# pic24.net
KiCad netlist of a schematic drawn in EasyEDA
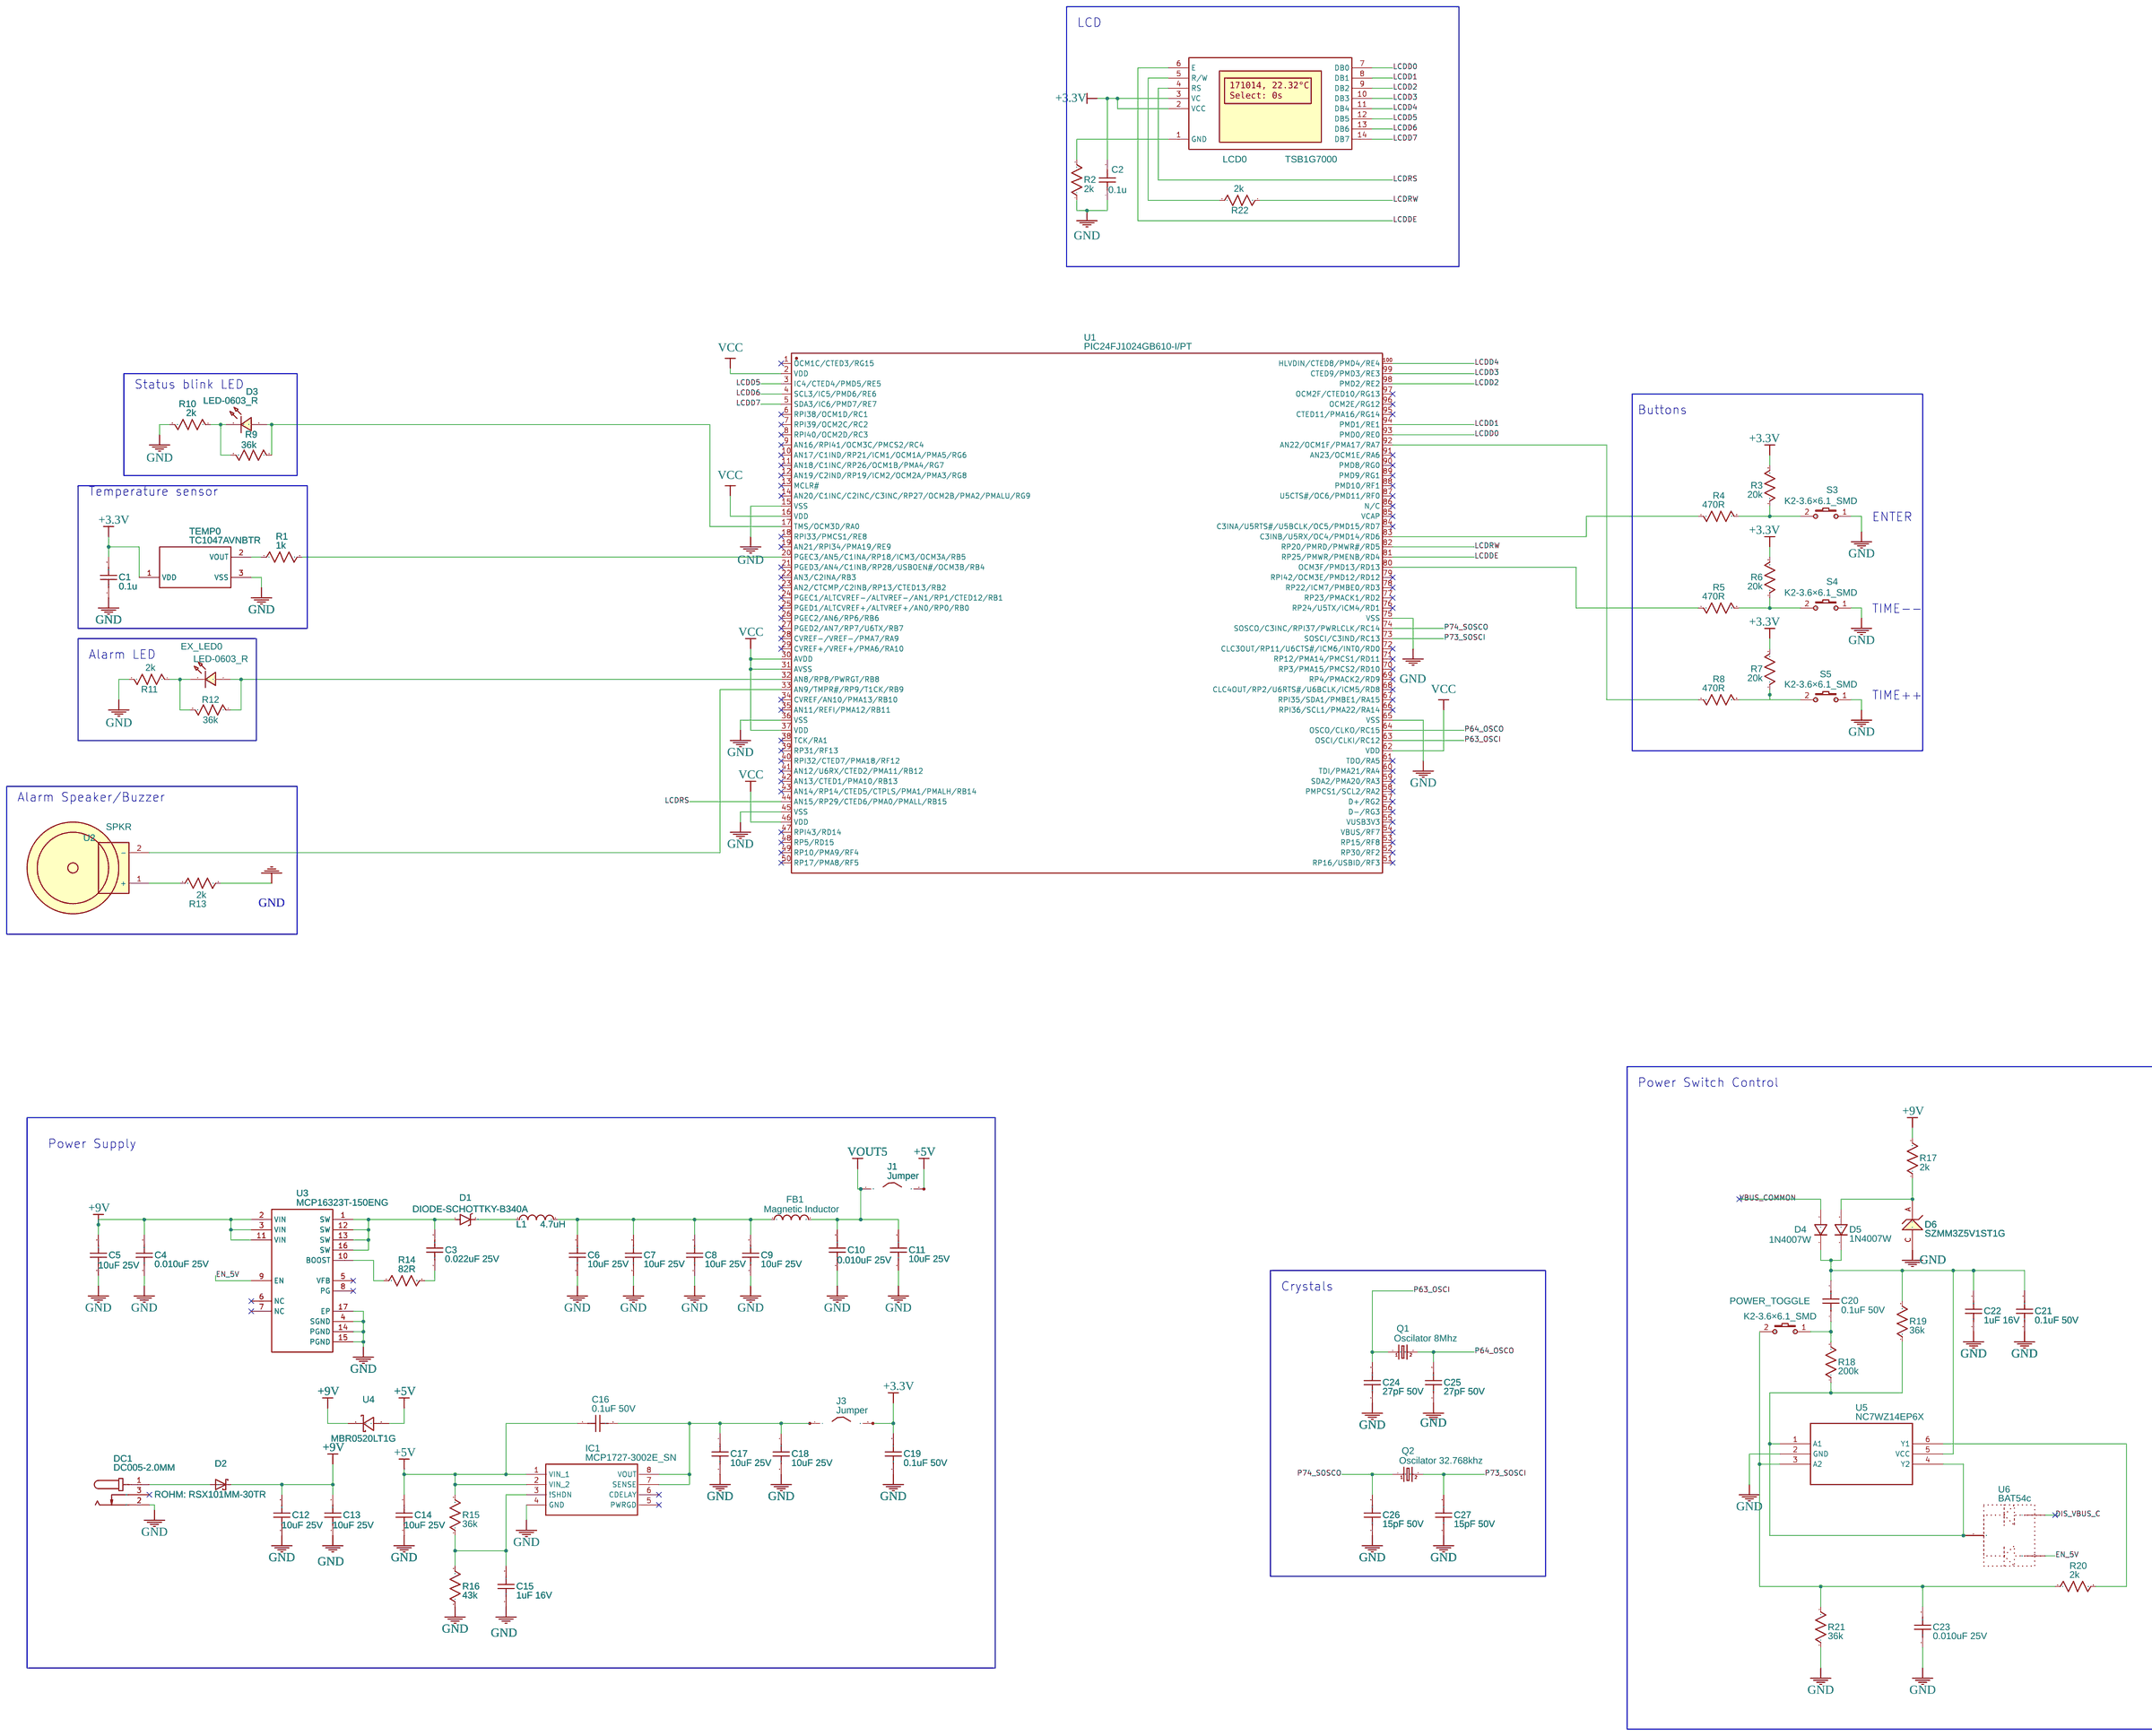
[diagram p0: schematic sheet]

(export (version "E")
  (design (tool "Eeschema 10.0.6"))
  (components
    (comp (ref "C1") (value "0.1u") (libsource (lib "") (part "C_0603_US")))
    (comp (ref "C2") (value "0.1u") (libsource (lib "") (part "C_0603_US")))
    (comp (ref "C3") (value "0.022uF 25V") (libsource (lib "") (part "C_0603_US")))
    (comp (ref "C4") (value "0.010uF 25V") (libsource (lib "") (part "C_0603_US")))
    (comp (ref "C5") (value "10uF 25V") (libsource (lib "") (part "C_0805_US")))
    (comp (ref "C6") (value "10uF 25V") (libsource (lib "") (part "C_0603_US")))
    (comp (ref "C7") (value "10uF 25V") (libsource (lib "") (part "C_0603_US")))
    (comp (ref "C8") (value "10uF 25V") (libsource (lib "") (part "C_0603_US")))
    (comp (ref "C9") (value "10uF 25V") (libsource (lib "") (part "C_0603_US")))
    (comp (ref "C10") (value "0.010uF 25V") (libsource (lib "") (part "C_0805_US")))
    (comp (ref "C11") (value "10uF 25V") (libsource (lib "") (part "C_0603_US")))
    (comp (ref "C12") (value "10uF 25V") (libsource (lib "") (part "C_0805_US")))
    (comp (ref "C13") (value "10uF 25V") (libsource (lib "") (part "C_0805_US")))
    (comp (ref "C14") (value "10uF 25V") (libsource (lib "") (part "C_0805_US")))
    (comp (ref "C15") (value "1uF 16V") (libsource (lib "") (part "C_0603_US")))
    (comp (ref "C16") (value "0.1uF 50V") (libsource (lib "") (part "C_0603_US_1")))
    (comp (ref "C17") (value "10uF 25V") (libsource (lib "") (part "C_0805_US_1")))
    (comp (ref "C18") (value "10uF 25V") (libsource (lib "") (part "C_0805_US_1")))
    (comp (ref "C19") (value "0.1uF 50V") (libsource (lib "") (part "C_0603_US")))
    (comp (ref "C20") (value "0.1uF 50V") (libsource (lib "") (part "C_0603_US")))
    (comp (ref "C21") (value "0.1uF 50V") (libsource (lib "") (part "C_0603_US")))
    (comp (ref "C22") (value "1uF 16V") (libsource (lib "") (part "C_0603_US")))
    (comp (ref "C23") (value "0.010uF 25V") (libsource (lib "") (part "C_0603_US")))
    (comp (ref "C24") (value "27pF 50V") (libsource (lib "") (part "C_0603_US")))
    (comp (ref "C25") (value "27pF 50V") (libsource (lib "") (part "C_0603_US")))
    (comp (ref "C26") (value "15pF 50V") (libsource (lib "") (part "C_0603_US")))
    (comp (ref "C27") (value "15pF 50V") (libsource (lib "") (part "C_0603_US")))
    (comp (ref "D1") (value "DIODE-SCHOTTKY-B340A") (libsource (lib "") (part "DIODE-SCHOTTKY-B340A")))
    (comp (ref "D2")
      (value "ROHM: RSX101MM-30TR")
      (fields (field (name "BOM_Supplier Part") "755-RSX101MM-30TR"))
      (libsource (lib "") (part "ROHM{colon} RSX101MM-30TR"))
    )
    (comp (ref "D3")
      (value "LED-0603_R")
      (fields
        (field (name "BOM_Manufacturer Part") "19-217/R6C-AL1M2VY/3T")
        (field (name "BOM_Supplier Part") "C72044")
      )
      (libsource (lib "") (part "LED-0603_R"))
    )
    (comp (ref "D4")
      (value "1N4007W")
      (fields (field (name "BOM_Supplier Part") "C328592"))
      (libsource (lib "") (part "1N4007W"))
    )
    (comp (ref "D5")
      (value "1N4007W")
      (fields (field (name "BOM_Supplier Part") "C328592"))
      (libsource (lib "") (part "1N4007W"))
    )
    (comp (ref "D6") (value "SZMM3Z5V1ST1G") (libsource (lib "") (part "SZMM3Z5V1ST1G")))
    (comp (ref "DC1")
      (value "DC005-2.0MM")
      (fields (field (name "BOM_Supplier Part") "C111567"))
      (libsource (lib "") (part "DC005-2.0MM"))
    )
    (comp (ref "EX_LED0")
      (value "LED-0603_R")
      (fields
        (field (name "BOM_Manufacturer Part") "19-217/R6C-AL1M2VY/3T")
        (field (name "BOM_Supplier Part") "C72044")
      )
      (libsource (lib "") (part "LED-0603_R_1"))
    )
    (comp (ref "FB1") (value "Magnetic Inductor") (libsource (lib "") (part "INDUCTOR")))
    (comp (ref "IC1") (value "MCP1727-3002E_SN") (libsource (lib "") (part "MCP1727-3002E_SN")))
    (comp (ref "J1")
      (value "Jumper")
      (fields (field (name "BOM_Manufacturer Part") "NONE"))
      (libsource (lib "") (part "JUMPER"))
    )
    (comp (ref "J3")
      (value "Jumper")
      (fields (field (name "BOM_Manufacturer Part") "NONE"))
      (libsource (lib "") (part "JUMPER"))
    )
    (comp (ref "L1") (value "4.7uH") (libsource (lib "") (part "L0603_US")))
    (comp (ref "LCD0") (value "TSB1G7000") (libsource (lib "") (part "TSB1G7000")))
    (comp (ref "POWER_TOGGLE")
      (value "K2-3.6×6.1_SMD")
      (fields
        (field (name "BOM_Manufacturer Part") "K2-1107ST-A4SW-06")
        (field (name "BOM_Supplier Part") "C118141")
      )
      (libsource (lib "") (part "K2-3.6×6.1_SMD_1"))
    )
    (comp (ref "Q1") (value "Oscilator 8Mhz") (libsource (lib "") (part "Oscilator 8Mhz")))
    (comp (ref "Q2") (value "Oscilator 32.768khz") (libsource (lib "") (part "Oscilator 8Mhz")))
    (comp (ref "R1") (value "1k") (libsource (lib "") (part "R_0603_US_3")))
    (comp (ref "R2") (value "2k") (libsource (lib "") (part "R_0603_US_1")))
    (comp (ref "R3") (value "20k") (libsource (lib "") (part "R_0603_US_4")))
    (comp (ref "R4") (value "470R") (libsource (lib "") (part "R_0603_US_2")))
    (comp (ref "R5") (value "470R") (libsource (lib "") (part "R_0603_US_2")))
    (comp (ref "R6") (value "20k") (libsource (lib "") (part "R_0603_US_4")))
    (comp (ref "R7") (value "20k") (libsource (lib "") (part "R_0603_US_4")))
    (comp (ref "R8") (value "470R") (libsource (lib "") (part "R_0603_US_2")))
    (comp (ref "R9") (value "36k") (libsource (lib "") (part "R_0603_US")))
    (comp (ref "R10") (value "2k") (libsource (lib "") (part "R_0603_US")))
    (comp (ref "R11") (value "2k") (libsource (lib "") (part "R_0603_US")))
    (comp (ref "R12") (value "36k") (libsource (lib "") (part "R_0603_US")))
    (comp (ref "R13") (value "2k") (libsource (lib "") (part "R_0603_US_5")))
    (comp (ref "R14") (value "82R") (libsource (lib "") (part "R_0603_US_3")))
    (comp (ref "R15") (value "36k") (libsource (lib "") (part "R_0603_US_1")))
    (comp (ref "R16") (value "43k") (libsource (lib "") (part "R_0603_US_1")))
    (comp (ref "R17") (value "2k") (libsource (lib "") (part "R_0603_US_1")))
    (comp (ref "R18") (value "200k") (libsource (lib "") (part "R_0603_US_1")))
    (comp (ref "R19") (value "36k") (libsource (lib "") (part "R_0603_US_1")))
    (comp (ref "R20") (value "2k") (libsource (lib "") (part "R_0603_US_3")))
    (comp (ref "R21") (value "36k") (libsource (lib "") (part "R_0603_US_1")))
    (comp (ref "R22") (value "2k") (libsource (lib "") (part "R_0603_US_3")))
    (comp (ref "S3")
      (value "K2-3.6×6.1_SMD")
      (fields
        (field (name "BOM_Manufacturer Part") "K2-1107ST-A4SW-06")
        (field (name "BOM_Supplier Part") "C118141")
      )
      (libsource (lib "") (part "K2-3.6×6.1_SMD"))
    )
    (comp (ref "S4")
      (value "K2-3.6×6.1_SMD")
      (fields
        (field (name "BOM_Manufacturer Part") "K2-1107ST-A4SW-06")
        (field (name "BOM_Supplier Part") "C118141")
      )
      (libsource (lib "") (part "K2-3.6×6.1_SMD"))
    )
    (comp (ref "S5")
      (value "K2-3.6×6.1_SMD")
      (fields
        (field (name "BOM_Manufacturer Part") "K2-1107ST-A4SW-06")
        (field (name "BOM_Supplier Part") "C118141")
      )
      (libsource (lib "") (part "K2-3.6×6.1_SMD"))
    )
    (comp (ref "TEMP0")
      (value "TC1047AVNBTR")
      (fields (field (name "BOM_Supplier Part") "C50052"))
      (libsource (lib "") (part "TC1047AVNBTR"))
    )
    (comp (ref "U1")
      (value "PIC24FJ1024GB610-I/PT")
      (fields (field (name "BOM_Supplier Part") "C635616"))
      (libsource (lib "") (part "PIC24FJ1024GB610-I/PT"))
    )
    (comp (ref "U2") (value "SPKR") (libsource (lib "") (part "SPKR")))
    (comp (ref "U3") (value "MCP16323T-150ENG") (libsource (lib "") (part "MCP16323T-150ENG")))
    (comp (ref "U4") (value "MBR0520LT1G") (libsource (lib "") (part "MBR0520LT1G")))
    (comp (ref "U5") (value "NC7WZ14EP6X") (libsource (lib "") (part "NC7WZ14EP6X")))
    (comp (ref "U6") (value "BAT54c") (libsource (lib "") (part "BAT54c")))
  )
  (nets
    (net (code "1") (name "+3.3V") (class "Default")
      (node (ref "C1") (pin "2") (pinfunction "2_2") (pintype "unspecified"))
      (node (ref "C19") (pin "2") (pinfunction "2_2") (pintype "unspecified"))
      (node (ref "C2") (pin "2") (pinfunction "2_2") (pintype "unspecified"))
      (node (ref "J3") (pin "2") (pinfunction "2_2") (pintype "unspecified"))
      (node (ref "LCD0") (pin "2") (pinfunction "VCC_2") (pintype "unspecified"))
      (node (ref "LCD0") (pin "3") (pinfunction "VC_3") (pintype "unspecified"))
      (node (ref "R3") (pin "2") (pinfunction "2_2") (pintype "unspecified"))
      (node (ref "R6") (pin "2") (pinfunction "2_2") (pintype "unspecified"))
      (node (ref "R7") (pin "2") (pinfunction "2_2") (pintype "unspecified"))
      (node (ref "TEMP0") (pin "1") (pinfunction "VDD_1") (pintype "passive"))
    )
    (net (code "2") (name "+5V") (class "Default")
      (node (ref "C14") (pin "2") (pinfunction "2_2") (pintype "unspecified"))
      (node (ref "C16") (pin "1") (pinfunction "1_1") (pintype "unspecified"))
      (node (ref "IC1") (pin "1") (pinfunction "VIN_1_1") (pintype "bidirectional"))
      (node (ref "IC1") (pin "2") (pinfunction "VIN_2_2") (pintype "bidirectional"))
      (node (ref "J1") (pin "2") (pinfunction "2_2") (pintype "unspecified"))
      (node (ref "R15") (pin "2") (pinfunction "2_2") (pintype "unspecified"))
      (node (ref "U4") (pin "1") (pinfunction "A_1") (pintype "unspecified"))
    )
    (net (code "3") (name "+9V") (class "Default")
      (node (ref "C12") (pin "2") (pinfunction "2_2") (pintype "unspecified"))
      (node (ref "C13") (pin "2") (pinfunction "2_2") (pintype "unspecified"))
      (node (ref "C4") (pin "2") (pinfunction "2_2") (pintype "unspecified"))
      (node (ref "C5") (pin "2") (pinfunction "2_2") (pintype "unspecified"))
      (node (ref "D2") (pin "2") (pinfunction "C_2") (pintype "unspecified"))
      (node (ref "R17") (pin "2") (pinfunction "2_2") (pintype "unspecified"))
      (node (ref "U3") (pin "11") (pinfunction "VIN_11") (pintype "passive"))
      (node (ref "U3") (pin "2") (pinfunction "VIN_2") (pintype "passive"))
      (node (ref "U3") (pin "3") (pinfunction "VIN_3") (pintype "passive"))
      (node (ref "U4") (pin "2") (pinfunction "K_2") (pintype "unspecified"))
    )
    (net (code "4") (name "/DIS_VBUS_C") (class "Default")
      (node (ref "U6") (pin "4") (pinfunction "4_4") (pintype "unspecified+no_connect"))
    )
    (net (code "5") (name "/EN_5V") (class "Default")
      (node (ref "U3") (pin "9") (pinfunction "EN_9") (pintype "unspecified"))
      (node (ref "U6") (pin "5") (pinfunction "5_5") (pintype "unspecified"))
    )
    (net (code "6") (name "/LCDD0") (class "Default")
      (node (ref "LCD0") (pin "7") (pinfunction "DB0_7") (pintype "unspecified"))
      (node (ref "U1") (pin "93") (pinfunction "PMD0/RE0_93") (pintype "unspecified"))
    )
    (net (code "7") (name "/LCDD1") (class "Default")
      (node (ref "LCD0") (pin "8") (pinfunction "DB1_8") (pintype "unspecified"))
      (node (ref "U1") (pin "94") (pinfunction "PMD1/RE1_94") (pintype "unspecified"))
    )
    (net (code "8") (name "/LCDD2") (class "Default")
      (node (ref "LCD0") (pin "9") (pinfunction "DB2_9") (pintype "unspecified"))
      (node (ref "U1") (pin "98") (pinfunction "PMD2/RE2_98") (pintype "unspecified"))
    )
    (net (code "9") (name "/LCDD3") (class "Default")
      (node (ref "LCD0") (pin "10") (pinfunction "DB3_10") (pintype "unspecified"))
      (node (ref "U1") (pin "99") (pinfunction "CTED9/PMD3/RE3_99") (pintype "unspecified"))
    )
    (net (code "10") (name "/LCDD4") (class "Default")
      (node (ref "LCD0") (pin "11") (pinfunction "DB4_11") (pintype "unspecified"))
      (node (ref "U1") (pin "100") (pinfunction "HLVDIN/CTED8/PMD4/RE4_100") (pintype "unspecified"))
    )
    (net (code "11") (name "/LCDD5") (class "Default")
      (node (ref "LCD0") (pin "12") (pinfunction "DB5_12") (pintype "unspecified"))
      (node (ref "U1") (pin "3") (pinfunction "IC4/CTED4/PMD5/RE5_3") (pintype "unspecified"))
    )
    (net (code "12") (name "/LCDD6") (class "Default")
      (node (ref "LCD0") (pin "13") (pinfunction "DB6_13") (pintype "unspecified"))
      (node (ref "U1") (pin "4") (pinfunction "SCL3/IC5/PMD6/RE6_4") (pintype "unspecified"))
    )
    (net (code "13") (name "/LCDD7") (class "Default")
      (node (ref "LCD0") (pin "14") (pinfunction "DB7_14") (pintype "unspecified"))
      (node (ref "U1") (pin "5") (pinfunction "SDA3/IC6/PMD7/RE7_5") (pintype "unspecified"))
    )
    (net (code "14") (name "/LCDDE") (class "Default")
      (node (ref "LCD0") (pin "6") (pinfunction "E_6") (pintype "unspecified"))
      (node (ref "U1") (pin "81") (pinfunction "RP25/PMWR/PMENB/RD4_81") (pintype "unspecified"))
    )
    (net (code "15") (name "/LCDRS") (class "Default")
      (node (ref "LCD0") (pin "4") (pinfunction "RS_4") (pintype "unspecified"))
      (node (ref "U1") (pin "44") (pinfunction "AN15/RP29/CTED6/PMA0/PMALL/RB15_44") (pintype "unspecified"))
    )
    (net (code "16") (name "/LCDRW") (class "Default")
      (node (ref "R22") (pin "2") (pinfunction "2_2") (pintype "unspecified"))
      (node (ref "U1") (pin "82") (pinfunction "RP20/PMRD/PMWR#/RD5_82") (pintype "unspecified"))
    )
    (net (code "17") (name "/P63_OSCI") (class "Default")
      (node (ref "C24") (pin "2") (pinfunction "2_2") (pintype "unspecified"))
      (node (ref "Q1") (pin "1") (pinfunction "XTAL1_1") (pintype "unspecified"))
      (node (ref "U1") (pin "63") (pinfunction "OSCI/CLKI/RC12_63") (pintype "unspecified"))
    )
    (net (code "18") (name "/P64_OSCO") (class "Default")
      (node (ref "C25") (pin "2") (pinfunction "2_2") (pintype "unspecified"))
      (node (ref "Q1") (pin "2") (pinfunction "XTAL2_2") (pintype "unspecified"))
      (node (ref "U1") (pin "64") (pinfunction "OSCO/CLKO/RC15_64") (pintype "unspecified"))
    )
    (net (code "19") (name "/P73_SOSCI") (class "Default")
      (node (ref "C27") (pin "2") (pinfunction "2_2") (pintype "unspecified"))
      (node (ref "Q2") (pin "2") (pinfunction "XTAL2_2") (pintype "unspecified"))
      (node (ref "U1") (pin "73") (pinfunction "SOSCI/C3IND/RC13_73") (pintype "unspecified"))
    )
    (net (code "20") (name "/P74_SOSCO") (class "Default")
      (node (ref "C26") (pin "2") (pinfunction "2_2") (pintype "unspecified"))
      (node (ref "Q2") (pin "1") (pinfunction "XTAL1_1") (pintype "unspecified"))
      (node (ref "U1") (pin "74") (pinfunction "SOSCO/C3INC/RPI37/PWRLCLK/RC14_74") (pintype "unspecified"))
    )
    (net (code "21") (name "/VBUS_COMMON") (class "Default")
      (node (ref "D4") (pin "2") (pinfunction "2_2") (pintype "unspecified+no_connect"))
    )
    (net (code "22") (name "GND") (class "Default")
      (node (ref "C1") (pin "1") (pinfunction "1_1") (pintype "unspecified"))
      (node (ref "C10") (pin "1") (pinfunction "1_1") (pintype "unspecified"))
      (node (ref "C11") (pin "1") (pinfunction "1_1") (pintype "unspecified"))
      (node (ref "C12") (pin "1") (pinfunction "1_1") (pintype "unspecified"))
      (node (ref "C13") (pin "1") (pinfunction "1_1") (pintype "unspecified"))
      (node (ref "C14") (pin "1") (pinfunction "1_1") (pintype "unspecified"))
      (node (ref "C15") (pin "1") (pinfunction "1_1") (pintype "unspecified"))
      (node (ref "C17") (pin "2") (pinfunction "2_2") (pintype "unspecified"))
      (node (ref "C18") (pin "2") (pinfunction "2_2") (pintype "unspecified"))
      (node (ref "C19") (pin "1") (pinfunction "1_1") (pintype "unspecified"))
      (node (ref "C2") (pin "1") (pinfunction "1_1") (pintype "unspecified"))
      (node (ref "C21") (pin "1") (pinfunction "1_1") (pintype "unspecified"))
      (node (ref "C22") (pin "1") (pinfunction "1_1") (pintype "unspecified"))
      (node (ref "C23") (pin "1") (pinfunction "1_1") (pintype "unspecified"))
      (node (ref "C24") (pin "1") (pinfunction "1_1") (pintype "unspecified"))
      (node (ref "C25") (pin "1") (pinfunction "1_1") (pintype "unspecified"))
      (node (ref "C26") (pin "1") (pinfunction "1_1") (pintype "unspecified"))
      (node (ref "C27") (pin "1") (pinfunction "1_1") (pintype "unspecified"))
      (node (ref "C4") (pin "1") (pinfunction "1_1") (pintype "unspecified"))
      (node (ref "C5") (pin "1") (pinfunction "1_1") (pintype "unspecified"))
      (node (ref "C6") (pin "1") (pinfunction "1_1") (pintype "unspecified"))
      (node (ref "C7") (pin "1") (pinfunction "1_1") (pintype "unspecified"))
      (node (ref "C8") (pin "1") (pinfunction "1_1") (pintype "unspecified"))
      (node (ref "C9") (pin "1") (pinfunction "1_1") (pintype "unspecified"))
      (node (ref "D6") (pin "C") (pinfunction "A_C") (pintype "unspecified"))
      (node (ref "DC1") (pin "2") (pinfunction "2_2") (pintype "unspecified"))
      (node (ref "IC1") (pin "4") (pinfunction "GND_4") (pintype "bidirectional"))
      (node (ref "R10") (pin "2") (pinfunction "2_2") (pintype "unspecified"))
      (node (ref "R11") (pin "2") (pinfunction "2_2") (pintype "unspecified"))
      (node (ref "R13") (pin "1") (pinfunction "1_1") (pintype "unspecified"))
      (node (ref "R16") (pin "1") (pinfunction "1_1") (pintype "unspecified"))
      (node (ref "R2") (pin "1") (pinfunction "1_1") (pintype "unspecified"))
      (node (ref "R21") (pin "1") (pinfunction "1_1") (pintype "unspecified"))
      (node (ref "S3") (pin "1") (pinfunction "1_1") (pintype "unspecified"))
      (node (ref "S4") (pin "1") (pinfunction "1_1") (pintype "unspecified"))
      (node (ref "S5") (pin "1") (pinfunction "1_1") (pintype "unspecified"))
      (node (ref "TEMP0") (pin "3") (pinfunction "VSS_3") (pintype "passive"))
      (node (ref "U1") (pin "15") (pinfunction "VSS_15") (pintype "unspecified"))
      (node (ref "U1") (pin "36") (pinfunction "VSS_36") (pintype "unspecified"))
      (node (ref "U1") (pin "45") (pinfunction "VSS_45") (pintype "unspecified"))
      (node (ref "U1") (pin "65") (pinfunction "VSS_65") (pintype "unspecified"))
      (node (ref "U1") (pin "75") (pinfunction "VSS_75") (pintype "unspecified"))
      (node (ref "U3") (pin "14") (pinfunction "PGND_14") (pintype "passive"))
      (node (ref "U3") (pin "15") (pinfunction "PGND_15") (pintype "passive"))
      (node (ref "U3") (pin "17") (pinfunction "EP_17") (pintype "passive"))
      (node (ref "U3") (pin "4") (pinfunction "SGND_4") (pintype "passive"))
      (node (ref "U5") (pin "2") (pinfunction "GND_2") (pintype "bidirectional"))
    )
    (net (code "23") (name "Net-(C3-Pad1)") (class "Default")
      (node (ref "C3") (pin "1") (pinfunction "1_1") (pintype "unspecified"))
      (node (ref "R14") (pin "2") (pinfunction "2_2") (pintype "unspecified"))
    )
    (net (code "24") (name "Net-(C3-Pad2)") (class "Default")
      (node (ref "C3") (pin "2") (pinfunction "2_2") (pintype "unspecified"))
      (node (ref "D1") (pin "A") (pinfunction "A_A") (pintype "unspecified"))
      (node (ref "U3") (pin "1") (pinfunction "SW_1") (pintype "passive"))
      (node (ref "U3") (pin "12") (pinfunction "SW_12") (pintype "passive"))
      (node (ref "U3") (pin "13") (pinfunction "SW_13") (pintype "passive"))
      (node (ref "U3") (pin "16") (pinfunction "SW_16") (pintype "passive"))
    )
    (net (code "25") (name "Net-(C6-Pad2)") (class "Default")
      (node (ref "C6") (pin "2") (pinfunction "2_2") (pintype "unspecified"))
      (node (ref "C7") (pin "2") (pinfunction "2_2") (pintype "unspecified"))
      (node (ref "C8") (pin "2") (pinfunction "2_2") (pintype "unspecified"))
      (node (ref "C9") (pin "2") (pinfunction "2_2") (pintype "unspecified"))
      (node (ref "FB1") (pin "1") (pinfunction "1_1") (pintype "unspecified"))
      (node (ref "L1") (pin "2") (pinfunction "2_2") (pintype "unspecified"))
    )
    (net (code "26") (name "Net-(C20-Pad1)") (class "Default")
      (node (ref "C20") (pin "1") (pinfunction "1_1") (pintype "unspecified"))
      (node (ref "POWER_TOGGLE") (pin "1") (pinfunction "1_1") (pintype "unspecified"))
      (node (ref "R18") (pin "2") (pinfunction "2_2") (pintype "unspecified"))
    )
    (net (code "27") (name "Net-(D1-PadC)") (class "Default")
      (node (ref "D1") (pin "C") (pinfunction "C_C") (pintype "unspecified"))
      (node (ref "L1") (pin "1") (pinfunction "1_1") (pintype "unspecified"))
    )
    (net (code "28") (name "Net-(D2-A)") (class "Default")
      (node (ref "D2") (pin "1") (pinfunction "A_1") (pintype "unspecified"))
      (node (ref "DC1") (pin "1") (pinfunction "1_1") (pintype "unspecified"))
    )
    (net (code "29") (name "Net-(D3-Pad2)") (class "Default")
      (node (ref "D3") (pin "2") (pinfunction "2_2") (pintype "unspecified"))
      (node (ref "R10") (pin "1") (pinfunction "1_1") (pintype "unspecified"))
      (node (ref "R9") (pin "2") (pinfunction "2_2") (pintype "unspecified"))
    )
    (net (code "30") (name "Net-(D6-K)") (class "Default")
      (node (ref "D5") (pin "2") (pinfunction "2_2") (pintype "unspecified"))
      (node (ref "D6") (pin "A") (pinfunction "K_A") (pintype "unspecified"))
      (node (ref "R17") (pin "1") (pinfunction "1_1") (pintype "unspecified"))
    )
    (net (code "31") (name "Net-(EX_LED0-Pad2)") (class "Default")
      (node (ref "EX_LED0") (pin "2") (pinfunction "2_2") (pintype "unspecified"))
      (node (ref "R11") (pin "1") (pinfunction "1_1") (pintype "unspecified"))
      (node (ref "R12") (pin "2") (pinfunction "2_2") (pintype "unspecified"))
    )
    (net (code "32") (name "Net-(IC1-!SHDN)") (class "Default")
      (node (ref "C15") (pin "2") (pinfunction "2_2") (pintype "unspecified"))
      (node (ref "IC1") (pin "3") (pinfunction "!SHDN_3") (pintype "bidirectional"))
      (node (ref "R15") (pin "1") (pinfunction "1_1") (pintype "unspecified"))
      (node (ref "R16") (pin "2") (pinfunction "2_2") (pintype "unspecified"))
    )
    (net (code "33") (name "Net-(IC1-SENSE)") (class "Default")
      (node (ref "C16") (pin "2") (pinfunction "2_2") (pintype "unspecified"))
      (node (ref "C17") (pin "1") (pinfunction "1_1") (pintype "unspecified"))
      (node (ref "C18") (pin "1") (pinfunction "1_1") (pintype "unspecified"))
      (node (ref "IC1") (pin "7") (pinfunction "SENSE_7") (pintype "bidirectional"))
      (node (ref "IC1") (pin "8") (pinfunction "VOUT_8") (pintype "bidirectional"))
      (node (ref "J3") (pin "1") (pinfunction "1_1") (pintype "unspecified"))
    )
    (net (code "34") (name "Net-(LCD0-GND)") (class "Default")
      (node (ref "LCD0") (pin "1") (pinfunction "GND_1") (pintype "unspecified"))
      (node (ref "R2") (pin "2") (pinfunction "2_2") (pintype "unspecified"))
    )
    (net (code "35") (name "Net-(LCD0-R{slash}W)") (class "Default")
      (node (ref "LCD0") (pin "5") (pinfunction "R/W_5") (pintype "unspecified"))
      (node (ref "R22") (pin "1") (pinfunction "1_1") (pintype "unspecified"))
    )
    (net (code "36") (name "Net-(R3-Pad1)") (class "Default")
      (node (ref "R3") (pin "1") (pinfunction "1_1") (pintype "unspecified"))
      (node (ref "R4") (pin "2") (pinfunction "2_2") (pintype "unspecified"))
      (node (ref "S3") (pin "2") (pinfunction "2_2") (pintype "unspecified"))
    )
    (net (code "37") (name "Net-(R5-Pad2)") (class "Default")
      (node (ref "R5") (pin "2") (pinfunction "2_2") (pintype "unspecified"))
      (node (ref "R6") (pin "1") (pinfunction "1_1") (pintype "unspecified"))
      (node (ref "S4") (pin "2") (pinfunction "2_2") (pintype "unspecified"))
    )
    (net (code "38") (name "Net-(R7-Pad1)") (class "Default")
      (node (ref "R7") (pin "1") (pinfunction "1_1") (pintype "unspecified"))
      (node (ref "R8") (pin "2") (pinfunction "2_2") (pintype "unspecified"))
      (node (ref "S5") (pin "2") (pinfunction "2_2") (pintype "unspecified"))
    )
    (net (code "39") (name "Net-(TEMP0-VOUT)") (class "Default")
      (node (ref "R1") (pin "1") (pinfunction "1_1") (pintype "unspecified"))
      (node (ref "TEMP0") (pin "2") (pinfunction "VOUT_2") (pintype "passive"))
    )
    (net (code "40") (name "Net-(U1-AN8{slash}RP8{slash}PWRGT{slash}RB8)") (class "Default")
      (node (ref "EX_LED0") (pin "1") (pinfunction "1_1") (pintype "unspecified"))
      (node (ref "R12") (pin "1") (pinfunction "1_1") (pintype "unspecified"))
      (node (ref "U1") (pin "32") (pinfunction "AN8/RP8/PWRGT/RB8_32") (pintype "unspecified"))
    )
    (net (code "41") (name "Net-(U1-AN9{slash}TMPR#{slash}RP9{slash}T1CK{slash}RB9)") (class "Default")
      (node (ref "U1") (pin "33") (pinfunction "AN9/TMPR#/RP9/T1CK/RB9_33") (pintype "unspecified"))
      (node (ref "U2") (pin "2") (pinfunction "-_2") (pintype "unspecified"))
    )
    (net (code "42") (name "Net-(U1-AN22{slash}OCM1F{slash}PMA17{slash}RA7)") (class "Default")
      (node (ref "R8") (pin "1") (pinfunction "1_1") (pintype "unspecified"))
      (node (ref "U1") (pin "92") (pinfunction "AN22/OCM1F/PMA17/RA7_92") (pintype "unspecified"))
    )
    (net (code "43") (name "Net-(U1-C3INB{slash}U5RX{slash}OC4{slash}PMD14{slash}RD6)") (class "Default")
      (node (ref "R4") (pin "1") (pinfunction "1_1") (pintype "unspecified"))
      (node (ref "U1") (pin "83") (pinfunction "C3INB/U5RX/OC4/PMD14/RD6_83") (pintype "unspecified"))
    )
    (net (code "44") (name "Net-(U1-OCM3F{slash}PMD13{slash}RD13)") (class "Default")
      (node (ref "R5") (pin "1") (pinfunction "1_1") (pintype "unspecified"))
      (node (ref "U1") (pin "80") (pinfunction "OCM3F/PMD13/RD13_80") (pintype "unspecified"))
    )
    (net (code "45") (name "Net-(U1-PGEC3{slash}AN5{slash}C1INA{slash}RP18{slash}ICM3{slash}OCM3A{slash}RB5)") (class "Default")
      (node (ref "R1") (pin "2") (pinfunction "2_2") (pintype "unspecified"))
      (node (ref "U1") (pin "20") (pinfunction "PGEC3/AN5/C1INA/RP18/ICM3/OCM3A/RB5_20") (pintype "unspecified"))
    )
    (net (code "46") (name "Net-(U1-TMS{slash}OCM3D{slash}RA0)") (class "Default")
      (node (ref "D3") (pin "1") (pinfunction "1_1") (pintype "unspecified"))
      (node (ref "R9") (pin "1") (pinfunction "1_1") (pintype "unspecified"))
      (node (ref "U1") (pin "17") (pinfunction "TMS/OCM3D/RA0_17") (pintype "unspecified"))
    )
    (net (code "47") (name "Net-(U2-+)") (class "Default")
      (node (ref "R13") (pin "2") (pinfunction "2_2") (pintype "unspecified"))
      (node (ref "U2") (pin "1") (pinfunction "+_1") (pintype "unspecified"))
    )
    (net (code "48") (name "Net-(U3-BOOST)") (class "Default")
      (node (ref "R14") (pin "1") (pinfunction "1_1") (pintype "unspecified"))
      (node (ref "U3") (pin "10") (pinfunction "BOOST_10") (pintype "passive"))
    )
    (net (code "49") (name "Net-(U5-A1)") (class "Default")
      (node (ref "R18") (pin "1") (pinfunction "1_1") (pintype "unspecified"))
      (node (ref "R19") (pin "1") (pinfunction "1_1") (pintype "unspecified"))
      (node (ref "U5") (pin "1") (pinfunction "A1_1") (pintype "input"))
      (node (ref "U5") (pin "4") (pinfunction "Y2_4") (pintype "output"))
      (node (ref "U6") (pin "6") (pinfunction "6_6") (pintype "unspecified"))
    )
    (net (code "50") (name "Net-(U5-A2)") (class "Default")
      (node (ref "C23") (pin "2") (pinfunction "2_2") (pintype "unspecified"))
      (node (ref "POWER_TOGGLE") (pin "2") (pinfunction "2_2") (pintype "unspecified"))
      (node (ref "R20") (pin "1") (pinfunction "1_1") (pintype "unspecified"))
      (node (ref "R21") (pin "2") (pinfunction "2_2") (pintype "unspecified"))
      (node (ref "U5") (pin "3") (pinfunction "A2_3") (pintype "input"))
    )
    (net (code "51") (name "Net-(U5-VCC)") (class "Default")
      (node (ref "C20") (pin "2") (pinfunction "2_2") (pintype "unspecified"))
      (node (ref "C21") (pin "2") (pinfunction "2_2") (pintype "unspecified"))
      (node (ref "C22") (pin "2") (pinfunction "2_2") (pintype "unspecified"))
      (node (ref "D4") (pin "1") (pinfunction "1_1") (pintype "unspecified"))
      (node (ref "D5") (pin "1") (pinfunction "1_1") (pintype "unspecified"))
      (node (ref "R19") (pin "2") (pinfunction "2_2") (pintype "unspecified"))
      (node (ref "U5") (pin "5") (pinfunction "VCC_5") (pintype "bidirectional"))
    )
    (net (code "52") (name "Net-(U5-Y1)") (class "Default")
      (node (ref "R20") (pin "2") (pinfunction "2_2") (pintype "unspecified"))
      (node (ref "U5") (pin "6") (pinfunction "Y1_6") (pintype "output"))
    )
    (net (code "53") (name "VCC") (class "Default")
      (node (ref "U1") (pin "16") (pinfunction "VDD_16") (pintype "unspecified"))
      (node (ref "U1") (pin "2") (pinfunction "VDD_2") (pintype "unspecified"))
      (node (ref "U1") (pin "30") (pinfunction "AVDD_30") (pintype "unspecified"))
      (node (ref "U1") (pin "31") (pinfunction "AVSS_31") (pintype "unspecified"))
      (node (ref "U1") (pin "37") (pinfunction "VDD_37") (pintype "unspecified"))
      (node (ref "U1") (pin "46") (pinfunction "VDD_46") (pintype "unspecified"))
      (node (ref "U1") (pin "62") (pinfunction "VDD_62") (pintype "unspecified"))
    )
    (net (code "54") (name "VOUT5") (class "Default")
      (node (ref "C10") (pin "2") (pinfunction "2_2") (pintype "unspecified"))
      (node (ref "C11") (pin "2") (pinfunction "2_2") (pintype "unspecified"))
      (node (ref "FB1") (pin "2") (pinfunction "2_2") (pintype "unspecified"))
      (node (ref "J1") (pin "1") (pinfunction "1_1") (pintype "unspecified"))
    )
    (net (code "55") (name "unconnected-(DC1-Pad3)") (class "Default")
      (node (ref "DC1") (pin "3") (pinfunction "3_3") (pintype "unspecified+no_connect"))
    )
    (net (code "56") (name "unconnected-(IC1-CDELAY-Pad6)") (class "Default")
      (node (ref "IC1") (pin "6") (pinfunction "CDELAY_6") (pintype "bidirectional+no_connect"))
    )
    (net (code "57") (name "unconnected-(IC1-PWRGD-Pad5)") (class "Default")
      (node (ref "IC1") (pin "5") (pinfunction "PWRGD_5") (pintype "bidirectional+no_connect"))
    )
    (net (code "58") (name "unconnected-(U1-AN2{slash}CTCMP{slash}C2INB{slash}RP13{slash}CTED13{slash}RB2-Pad23)") (class "Default")
      (node (ref "U1") (pin "23") (pinfunction "AN2/CTCMP/C2INB/RP13/CTED13/RB2_23") (pintype "unspecified+no_connect"))
    )
    (net (code "59") (name "unconnected-(U1-AN3{slash}C2INA{slash}RB3-Pad22)") (class "Default")
      (node (ref "U1") (pin "22") (pinfunction "AN3/C2INA/RB3_22") (pintype "unspecified+no_connect"))
    )
    (net (code "60") (name "unconnected-(U1-AN11{slash}REFI{slash}PMA12{slash}RB11-Pad35)") (class "Default")
      (node (ref "U1") (pin "35") (pinfunction "AN11/REFI/PMA12/RB11_35") (pintype "unspecified+no_connect"))
    )
    (net (code "61") (name "unconnected-(U1-AN12{slash}U6RX{slash}CTED2{slash}PMA11{slash}RB12-Pad41)") (class "Default")
      (node (ref "U1") (pin "41") (pinfunction "AN12/U6RX/CTED2/PMA11/RB12_41") (pintype "unspecified+no_connect"))
    )
    (net (code "62") (name "unconnected-(U1-AN13{slash}CTED1{slash}PMA10{slash}RB13-Pad42)") (class "Default")
      (node (ref "U1") (pin "42") (pinfunction "AN13/CTED1/PMA10/RB13_42") (pintype "unspecified+no_connect"))
    )
    (net (code "63") (name "unconnected-(U1-AN14{slash}RP14{slash}CTED5{slash}CTPLS{slash}PMA1{slash}PMALH{slash}RB14-Pad43)") (class "Default")
      (node (ref "U1") (pin "43") (pinfunction "AN14/RP14/CTED5/CTPLS/PMA1/PMALH/RB14_43") (pintype "unspecified+no_connect"))
    )
    (net (code "64") (name "unconnected-(U1-AN16{slash}RPI41{slash}OCM3C{slash}PMCS2{slash}RC4-Pad9)") (class "Default")
      (node (ref "U1") (pin "9") (pinfunction "AN16/RPI41/OCM3C/PMCS2/RC4_9") (pintype "unspecified+no_connect"))
    )
    (net (code "65") (name "unconnected-(U1-AN17{slash}C1IND{slash}RP21{slash}ICM1{slash}OCM1A{slash}PMA5{slash}RG6-Pad10)") (class "Default")
      (node (ref "U1") (pin "10") (pinfunction "AN17/C1IND/RP21/ICM1/OCM1A/PMA5/RG6_10") (pintype "unspecified+no_connect"))
    )
    (net (code "66") (name "unconnected-(U1-AN18{slash}C1INC{slash}RP26{slash}OCM1B{slash}PMA4{slash}RG7-Pad11)") (class "Default")
      (node (ref "U1") (pin "11") (pinfunction "AN18/C1INC/RP26/OCM1B/PMA4/RG7_11") (pintype "unspecified+no_connect"))
    )
    (net (code "67") (name "unconnected-(U1-AN19{slash}C2IND{slash}RP19{slash}ICM2{slash}OCM2A{slash}PMA3{slash}RG8-Pad12)") (class "Default")
      (node (ref "U1") (pin "12") (pinfunction "AN19/C2IND/RP19/ICM2/OCM2A/PMA3/RG8_12") (pintype "unspecified+no_connect"))
    )
    (net (code "68") (name "unconnected-(U1-AN20{slash}C1INC{slash}C2INC{slash}C3INC{slash}RP27{slash}OCM2B{slash}PMA2{slash}PMALU{slash}RG9-Pad14)") (class "Default")
      (node (ref "U1") (pin "14") (pinfunction "AN20/C1INC/C2INC/C3INC/RP27/OCM2B/PMA2/PMALU/RG9_14") (pintype "unspecified+no_connect"))
    )
    (net (code "69") (name "unconnected-(U1-AN21{slash}RPI34{slash}PMA19{slash}RE9-Pad19)") (class "Default")
      (node (ref "U1") (pin "19") (pinfunction "AN21/RPI34/PMA19/RE9_19") (pintype "unspecified+no_connect"))
    )
    (net (code "70") (name "unconnected-(U1-AN23{slash}OCM1E{slash}RA6-Pad91)") (class "Default")
      (node (ref "U1") (pin "91") (pinfunction "AN23/OCM1E/RA6_91") (pintype "unspecified+no_connect"))
    )
    (net (code "71") (name "unconnected-(U1-C3INA{slash}U5RTS#{slash}U5BCLK{slash}OC5{slash}PMD15{slash}RD7-Pad84)") (class "Default")
      (node (ref "U1") (pin "84") (pinfunction "C3INA/U5RTS#/U5BCLK/OC5/PMD15/RD7_84") (pintype "unspecified+no_connect"))
    )
    (net (code "72") (name "unconnected-(U1-CLC3OUT{slash}RP11{slash}U6CTS#{slash}ICM6{slash}INT0{slash}RD0-Pad72)") (class "Default")
      (node (ref "U1") (pin "72") (pinfunction "CLC3OUT/RP11/U6CTS#/ICM6/INT0/RD0_72") (pintype "unspecified+no_connect"))
    )
    (net (code "73") (name "unconnected-(U1-CLC4OUT{slash}RP2{slash}U6RTS#{slash}U6BCLK{slash}ICM5{slash}RD8-Pad68)") (class "Default")
      (node (ref "U1") (pin "68") (pinfunction "CLC4OUT/RP2/U6RTS#/U6BCLK/ICM5/RD8_68") (pintype "unspecified+no_connect"))
    )
    (net (code "74") (name "unconnected-(U1-CTED11{slash}PMA16{slash}RG14-Pad95)") (class "Default")
      (node (ref "U1") (pin "95") (pinfunction "CTED11/PMA16/RG14_95") (pintype "unspecified+no_connect"))
    )
    (net (code "75") (name "unconnected-(U1-CVREF+{slash}VREF+{slash}PMA6{slash}RA10-Pad29)") (class "Default")
      (node (ref "U1") (pin "29") (pinfunction "CVREF+/VREF+/PMA6/RA10_29") (pintype "unspecified+no_connect"))
    )
    (net (code "76") (name "unconnected-(U1-CVREF-{slash}VREF-{slash}PMA7{slash}RA9-Pad28)") (class "Default")
      (node (ref "U1") (pin "28") (pinfunction "CVREF-/VREF-/PMA7/RA9_28") (pintype "unspecified+no_connect"))
    )
    (net (code "77") (name "unconnected-(U1-CVREF{slash}AN10{slash}PMA13{slash}RB10-Pad34)") (class "Default")
      (node (ref "U1") (pin "34") (pinfunction "CVREF/AN10/PMA13/RB10_34") (pintype "unspecified+no_connect"))
    )
    (net (code "78") (name "unconnected-(U1-D+{slash}RG2-Pad57)") (class "Default")
      (node (ref "U1") (pin "57") (pinfunction "D+/RG2_57") (pintype "unspecified+no_connect"))
    )
    (net (code "79") (name "unconnected-(U1-D-{slash}RG3-Pad56)") (class "Default")
      (node (ref "U1") (pin "56") (pinfunction "D-/RG3_56") (pintype "unspecified+no_connect"))
    )
    (net (code "80") (name "unconnected-(U1-MCLR#-Pad13)") (class "Default")
      (node (ref "U1") (pin "13") (pinfunction "MCLR#_13") (pintype "unspecified+no_connect"))
    )
    (net (code "81") (name "unconnected-(U1-N{slash}C-Pad86)") (class "Default")
      (node (ref "U1") (pin "86") (pinfunction "N/C_86") (pintype "unspecified+no_connect"))
    )
    (net (code "82") (name "unconnected-(U1-OCM1C{slash}CTED3{slash}RG15-Pad1)") (class "Default")
      (node (ref "U1") (pin "1") (pinfunction "OCM1C/CTED3/RG15_1") (pintype "unspecified+no_connect"))
    )
    (net (code "83") (name "unconnected-(U1-OCM2E{slash}RG12-Pad96)") (class "Default")
      (node (ref "U1") (pin "96") (pinfunction "OCM2E/RG12_96") (pintype "unspecified+no_connect"))
    )
    (net (code "84") (name "unconnected-(U1-OCM2F{slash}CTED10{slash}RG13-Pad97)") (class "Default")
      (node (ref "U1") (pin "97") (pinfunction "OCM2F/CTED10/RG13_97") (pintype "unspecified+no_connect"))
    )
    (net (code "85") (name "unconnected-(U1-PGEC1{slash}ALTCVREF-{slash}ALTVREF-{slash}AN1{slash}RP1{slash}CTED12{slash}RB1-Pad24)") (class "Default")
      (node (ref "U1") (pin "24") (pinfunction "PGEC1/ALTCVREF-/ALTVREF-/AN1/RP1/CTED12/RB1_24") (pintype "unspecified+no_connect"))
    )
    (net (code "86") (name "unconnected-(U1-PGEC2{slash}AN6{slash}RP6{slash}RB6-Pad26)") (class "Default")
      (node (ref "U1") (pin "26") (pinfunction "PGEC2/AN6/RP6/RB6_26") (pintype "unspecified+no_connect"))
    )
    (net (code "87") (name "unconnected-(U1-PGED1{slash}ALTCVREF+{slash}ALTVREF+{slash}AN0{slash}RP0{slash}RB0-Pad25)") (class "Default")
      (node (ref "U1") (pin "25") (pinfunction "PGED1/ALTCVREF+/ALTVREF+/AN0/RP0/RB0_25") (pintype "unspecified+no_connect"))
    )
    (net (code "88") (name "unconnected-(U1-PGED2{slash}AN7{slash}RP7{slash}U6TX{slash}RB7-Pad27)") (class "Default")
      (node (ref "U1") (pin "27") (pinfunction "PGED2/AN7/RP7/U6TX/RB7_27") (pintype "unspecified+no_connect"))
    )
    (net (code "89") (name "unconnected-(U1-PGED3{slash}AN4{slash}C1INB{slash}RP28{slash}USBOEN#{slash}OCM3B{slash}RB4-Pad21)") (class "Default")
      (node (ref "U1") (pin "21") (pinfunction "PGED3/AN4/C1INB/RP28/USBOEN#/OCM3B/RB4_21") (pintype "unspecified+no_connect"))
    )
    (net (code "90") (name "unconnected-(U1-PMD8{slash}RG0-Pad90)") (class "Default")
      (node (ref "U1") (pin "90") (pinfunction "PMD8/RG0_90") (pintype "unspecified+no_connect"))
    )
    (net (code "91") (name "unconnected-(U1-PMD9{slash}RG1-Pad89)") (class "Default")
      (node (ref "U1") (pin "89") (pinfunction "PMD9/RG1_89") (pintype "unspecified+no_connect"))
    )
    (net (code "92") (name "unconnected-(U1-PMD10{slash}RF1-Pad88)") (class "Default")
      (node (ref "U1") (pin "88") (pinfunction "PMD10/RF1_88") (pintype "unspecified+no_connect"))
    )
    (net (code "93") (name "unconnected-(U1-PMPCS1{slash}SCL2{slash}RA2-Pad58)") (class "Default")
      (node (ref "U1") (pin "58") (pinfunction "PMPCS1/SCL2/RA2_58") (pintype "unspecified+no_connect"))
    )
    (net (code "94") (name "unconnected-(U1-RP3{slash}PMA15{slash}PMCS2{slash}RD10-Pad70)") (class "Default")
      (node (ref "U1") (pin "70") (pinfunction "RP3/PMA15/PMCS2/RD10_70") (pintype "unspecified+no_connect"))
    )
    (net (code "95") (name "unconnected-(U1-RP4{slash}PMACK2{slash}RD9-Pad69)") (class "Default")
      (node (ref "U1") (pin "69") (pinfunction "RP4/PMACK2/RD9_69") (pintype "unspecified+no_connect"))
    )
    (net (code "96") (name "unconnected-(U1-RP5{slash}RD15-Pad48)") (class "Default")
      (node (ref "U1") (pin "48") (pinfunction "RP5/RD15_48") (pintype "unspecified+no_connect"))
    )
    (net (code "97") (name "unconnected-(U1-RP10{slash}PMA9{slash}RF4-Pad49)") (class "Default")
      (node (ref "U1") (pin "49") (pinfunction "RP10/PMA9/RF4_49") (pintype "unspecified+no_connect"))
    )
    (net (code "98") (name "unconnected-(U1-RP12{slash}PMA14{slash}PMCS1{slash}RD11-Pad71)") (class "Default")
      (node (ref "U1") (pin "71") (pinfunction "RP12/PMA14/PMCS1/RD11_71") (pintype "unspecified+no_connect"))
    )
    (net (code "99") (name "unconnected-(U1-RP15{slash}RF8-Pad53)") (class "Default")
      (node (ref "U1") (pin "53") (pinfunction "RP15/RF8_53") (pintype "unspecified+no_connect"))
    )
    (net (code "100") (name "unconnected-(U1-RP16{slash}USBID{slash}RF3-Pad51)") (class "Default")
      (node (ref "U1") (pin "51") (pinfunction "RP16/USBID/RF3_51") (pintype "unspecified+no_connect"))
    )
    (net (code "101") (name "unconnected-(U1-RP17{slash}PMA8{slash}RF5-Pad50)") (class "Default")
      (node (ref "U1") (pin "50") (pinfunction "RP17/PMA8/RF5_50") (pintype "unspecified+no_connect"))
    )
    (net (code "102") (name "unconnected-(U1-RP22{slash}ICM7{slash}PMBE0{slash}RD3-Pad78)") (class "Default")
      (node (ref "U1") (pin "78") (pinfunction "RP22/ICM7/PMBE0/RD3_78") (pintype "unspecified+no_connect"))
    )
    (net (code "103") (name "unconnected-(U1-RP23{slash}PMACK1{slash}RD2-Pad77)") (class "Default")
      (node (ref "U1") (pin "77") (pinfunction "RP23/PMACK1/RD2_77") (pintype "unspecified+no_connect"))
    )
    (net (code "104") (name "unconnected-(U1-RP24{slash}U5TX{slash}ICM4{slash}RD1-Pad76)") (class "Default")
      (node (ref "U1") (pin "76") (pinfunction "RP24/U5TX/ICM4/RD1_76") (pintype "unspecified+no_connect"))
    )
    (net (code "105") (name "unconnected-(U1-RP30{slash}RF2-Pad52)") (class "Default")
      (node (ref "U1") (pin "52") (pinfunction "RP30/RF2_52") (pintype "unspecified+no_connect"))
    )
    (net (code "106") (name "unconnected-(U1-RP31{slash}RF13-Pad39)") (class "Default")
      (node (ref "U1") (pin "39") (pinfunction "RP31/RF13_39") (pintype "unspecified+no_connect"))
    )
    (net (code "107") (name "unconnected-(U1-RPI32{slash}CTED7{slash}PMA18{slash}RF12-Pad40)") (class "Default")
      (node (ref "U1") (pin "40") (pinfunction "RPI32/CTED7/PMA18/RF12_40") (pintype "unspecified+no_connect"))
    )
    (net (code "108") (name "unconnected-(U1-RPI33{slash}PMCS1{slash}RE8-Pad18)") (class "Default")
      (node (ref "U1") (pin "18") (pinfunction "RPI33/PMCS1/RE8_18") (pintype "unspecified+no_connect"))
    )
    (net (code "109") (name "unconnected-(U1-RPI35{slash}SDA1{slash}PMBE1{slash}RA15-Pad67)") (class "Default")
      (node (ref "U1") (pin "67") (pinfunction "RPI35/SDA1/PMBE1/RA15_67") (pintype "unspecified+no_connect"))
    )
    (net (code "110") (name "unconnected-(U1-RPI36{slash}SCL1{slash}PMA22{slash}RA14-Pad66)") (class "Default")
      (node (ref "U1") (pin "66") (pinfunction "RPI36/SCL1/PMA22/RA14_66") (pintype "unspecified+no_connect"))
    )
    (net (code "111") (name "unconnected-(U1-RPI38{slash}OCM1D{slash}RC1-Pad6)") (class "Default")
      (node (ref "U1") (pin "6") (pinfunction "RPI38/OCM1D/RC1_6") (pintype "unspecified+no_connect"))
    )
    (net (code "112") (name "unconnected-(U1-RPI39{slash}OCM2C{slash}RC2-Pad7)") (class "Default")
      (node (ref "U1") (pin "7") (pinfunction "RPI39/OCM2C/RC2_7") (pintype "unspecified+no_connect"))
    )
    (net (code "113") (name "unconnected-(U1-RPI40{slash}OCM2D{slash}RC3-Pad8)") (class "Default")
      (node (ref "U1") (pin "8") (pinfunction "RPI40/OCM2D/RC3_8") (pintype "unspecified+no_connect"))
    )
    (net (code "114") (name "unconnected-(U1-RPI42{slash}OCM3E{slash}PMD12{slash}RD12-Pad79)") (class "Default")
      (node (ref "U1") (pin "79") (pinfunction "RPI42/OCM3E/PMD12/RD12_79") (pintype "unspecified+no_connect"))
    )
    (net (code "115") (name "unconnected-(U1-RPI43{slash}RD14-Pad47)") (class "Default")
      (node (ref "U1") (pin "47") (pinfunction "RPI43/RD14_47") (pintype "unspecified+no_connect"))
    )
    (net (code "116") (name "unconnected-(U1-SDA2{slash}PMA20{slash}RA3-Pad59)") (class "Default")
      (node (ref "U1") (pin "59") (pinfunction "SDA2/PMA20/RA3_59") (pintype "unspecified+no_connect"))
    )
    (net (code "117") (name "unconnected-(U1-TCK{slash}RA1-Pad38)") (class "Default")
      (node (ref "U1") (pin "38") (pinfunction "TCK/RA1_38") (pintype "unspecified+no_connect"))
    )
    (net (code "118") (name "unconnected-(U1-TDI{slash}PMA21{slash}RA4-Pad60)") (class "Default")
      (node (ref "U1") (pin "60") (pinfunction "TDI/PMA21/RA4_60") (pintype "unspecified+no_connect"))
    )
    (net (code "119") (name "unconnected-(U1-TDO{slash}RA5-Pad61)") (class "Default")
      (node (ref "U1") (pin "61") (pinfunction "TDO/RA5_61") (pintype "unspecified+no_connect"))
    )
    (net (code "120") (name "unconnected-(U1-U5CTS#{slash}OC6{slash}PMD11{slash}RF0-Pad87)") (class "Default")
      (node (ref "U1") (pin "87") (pinfunction "U5CTS#/OC6/PMD11/RF0_87") (pintype "unspecified+no_connect"))
    )
    (net (code "121") (name "unconnected-(U1-VBUS{slash}RF7-Pad54)") (class "Default")
      (node (ref "U1") (pin "54") (pinfunction "VBUS/RF7_54") (pintype "unspecified+no_connect"))
    )
    (net (code "122") (name "unconnected-(U1-VCAP-Pad85)") (class "Default")
      (node (ref "U1") (pin "85") (pinfunction "VCAP_85") (pintype "unspecified+no_connect"))
    )
    (net (code "123") (name "unconnected-(U1-VUSB3V3-Pad55)") (class "Default")
      (node (ref "U1") (pin "55") (pinfunction "VUSB3V3_55") (pintype "unspecified+no_connect"))
    )
    (net (code "124") (name "unconnected-(U3-NC-Pad6)") (class "Default")
      (node (ref "U3") (pin "6") (pinfunction "NC_6") (pintype "unspecified+no_connect"))
    )
    (net (code "125") (name "unconnected-(U3-NC-Pad7)") (class "Default")
      (node (ref "U3") (pin "7") (pinfunction "NC_7") (pintype "unspecified+no_connect"))
    )
    (net (code "126") (name "unconnected-(U3-PG-Pad8)") (class "Default")
      (node (ref "U3") (pin "8") (pinfunction "PG_8") (pintype "unspecified+no_connect"))
    )
    (net (code "127") (name "unconnected-(U3-VFB-Pad5)") (class "Default")
      (node (ref "U3") (pin "5") (pinfunction "VFB_5") (pintype "unspecified+no_connect"))
    )
  )
)
